# led.net
KiCad netlist of a schematic drawn in Altium Designer
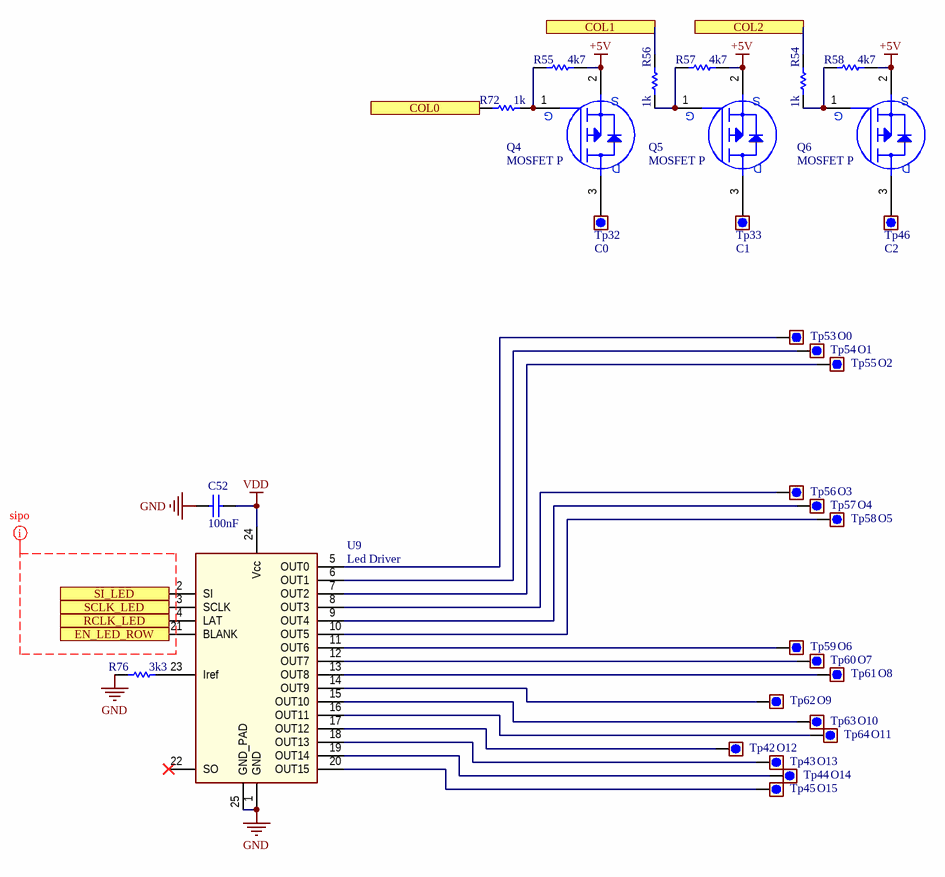
[diagram p0: led.SchDoc]

(export (version "E")
  (design (tool "Eeschema 10.0.6"))
  (components
    (comp (ref "C52")
      (value "100nF")
      (footprint "0603_[1608]")
      (description "Ceramic X7R 50V")
      (fields (field (name "PUBLISHER") "Altium Limited"))
      (libsource (lib "DEVELER_Library") (part "Cap"))
    )
    (comp (ref "Q4")
      (value "MOSFET P")
      (footprint "SOT-23")
      (description "IRLML5103TRPbF; DMG1013UW;")
      (libsource (lib "develer_library") (part "MOSFET-P 3pin"))
    )
    (comp (ref "Q5")
      (value "MOSFET P")
      (footprint "SOT-23")
      (description "IRLML5103TRPbF; DMG1013UW;")
      (libsource (lib "develer_library") (part "MOSFET-P 3pin"))
    )
    (comp (ref "Q6")
      (value "MOSFET P")
      (footprint "SOT-23")
      (description "IRLML5103TRPbF; DMG1013UW;")
      (libsource (lib "develer_library") (part "MOSFET-P 3pin"))
    )
    (comp (ref "R54")
      (value "1k")
      (footprint "0603_[1608]")
      (description "Resistor")
      (fields (field (name "PUBLISHER") "Altium Limited"))
      (libsource (lib "simboli") (part "Res1"))
    )
    (comp (ref "R55")
      (value "4k7")
      (footprint "0603_[1608]")
      (description "Resistor")
      (fields (field (name "PUBLISHER") "Altium Limited"))
      (libsource (lib "simboli") (part "Res1"))
    )
    (comp (ref "R56")
      (value "1k")
      (footprint "0603_[1608]")
      (description "Resistor")
      (fields (field (name "PUBLISHER") "Altium Limited"))
      (libsource (lib "simboli") (part "Res1"))
    )
    (comp (ref "R57")
      (value "4k7")
      (footprint "0603_[1608]")
      (description "Resistor")
      (fields (field (name "PUBLISHER") "Altium Limited"))
      (libsource (lib "simboli") (part "Res1"))
    )
    (comp (ref "R58")
      (value "4k7")
      (footprint "0603_[1608]")
      (description "Resistor")
      (fields (field (name "PUBLISHER") "Altium Limited"))
      (libsource (lib "simboli") (part "Res1"))
    )
    (comp (ref "R72")
      (value "1k")
      (footprint "0603_[1608]")
      (description "Resistor")
      (fields (field (name "PUBLISHER") "Altium Limited"))
      (libsource (lib "simboli") (part "Res1"))
    )
    (comp (ref "R76")
      (value "3k3")
      (footprint "0805_[2012]")
      (description "Resistor")
      (fields (field (name "PUBLISHER") "Altium Limited"))
      (libsource (lib "simboli") (part "Res1"))
    )
    (comp (ref "Tp32")
      (value "C0")
      (footprint "TEST_POINT_THD_D1.6mm_oval")
      (description "Test point")
      (libsource (lib "DEVELER_Library") (part "Test_point"))
    )
    (comp (ref "Tp33")
      (value "C1")
      (footprint "TEST_POINT_THD_D1.6mm_oval")
      (description "Test point")
      (libsource (lib "DEVELER_Library") (part "Test_point"))
    )
    (comp (ref "Tp42")
      (value "O12")
      (footprint "TEST_POINT_THD_D1.6mm_oval")
      (description "Test point")
      (libsource (lib "") (part "Test_point_1"))
    )
    (comp (ref "Tp43")
      (value "O13")
      (footprint "TEST_POINT_THD_D1.6mm_oval")
      (description "Test point")
      (libsource (lib "") (part "Test_point_1"))
    )
    (comp (ref "Tp44")
      (value "O14")
      (footprint "TEST_POINT_THD_D1.6mm_oval")
      (description "Test point")
      (libsource (lib "") (part "Test_point_1"))
    )
    (comp (ref "Tp45")
      (value "O15")
      (footprint "TEST_POINT_THD_D1.6mm_oval")
      (description "Test point")
      (libsource (lib "") (part "Test_point_1"))
    )
    (comp (ref "Tp46")
      (value "C2")
      (footprint "TEST_POINT_THD_D1.6mm_oval")
      (description "Test point")
      (libsource (lib "DEVELER_Library") (part "Test_point"))
    )
    (comp (ref "Tp53")
      (value "O0")
      (footprint "TEST_POINT_THD_D1.6mm_oval")
      (description "Test point")
      (libsource (lib "") (part "Test_point_1"))
    )
    (comp (ref "Tp54")
      (value "O1")
      (footprint "TEST_POINT_THD_D1.6mm_oval")
      (description "Test point")
      (libsource (lib "") (part "Test_point_1"))
    )
    (comp (ref "Tp55")
      (value "O2")
      (footprint "TEST_POINT_THD_D1.6mm_oval")
      (description "Test point")
      (libsource (lib "") (part "Test_point_1"))
    )
    (comp (ref "Tp56")
      (value "O3")
      (footprint "TEST_POINT_THD_D1.6mm_oval")
      (description "Test point")
      (libsource (lib "") (part "Test_point_1"))
    )
    (comp (ref "Tp57")
      (value "O4")
      (footprint "TEST_POINT_THD_D1.6mm_oval")
      (description "Test point")
      (libsource (lib "") (part "Test_point_1"))
    )
    (comp (ref "Tp58")
      (value "O5")
      (footprint "TEST_POINT_THD_D1.6mm_oval")
      (description "Test point")
      (libsource (lib "") (part "Test_point_1"))
    )
    (comp (ref "Tp59")
      (value "O6")
      (footprint "TEST_POINT_THD_D1.6mm_oval")
      (description "Test point")
      (libsource (lib "") (part "Test_point_1"))
    )
    (comp (ref "Tp60")
      (value "O7")
      (footprint "TEST_POINT_THD_D1.6mm_oval")
      (description "Test point")
      (libsource (lib "") (part "Test_point_1"))
    )
    (comp (ref "Tp61")
      (value "O8")
      (footprint "TEST_POINT_THD_D1.6mm_oval")
      (description "Test point")
      (libsource (lib "") (part "Test_point_1"))
    )
    (comp (ref "Tp62")
      (value "O9")
      (footprint "TEST_POINT_THD_D1.6mm_oval")
      (description "Test point")
      (libsource (lib "") (part "Test_point_1"))
    )
    (comp (ref "Tp63")
      (value "O10")
      (footprint "TEST_POINT_THD_D1.6mm_oval")
      (description "Test point")
      (libsource (lib "") (part "Test_point_1"))
    )
    (comp (ref "Tp64")
      (value "O11")
      (footprint "TEST_POINT_THD_D1.6mm_oval")
      (description "Test point")
      (libsource (lib "") (part "Test_point_1"))
    )
    (comp (ref "U9")
      (value "Led Driver")
      (footprint "TSOP65P640X120_HS-25N")
      (description "(Texas TLC5928; ST STP16CP05)")
      (libsource (lib "develer_library") (part "Led_driver"))
    )
  )
  (nets
    (net (code "1") (name "+5V") (class "Default")
      (node (ref "Q4") (pin "2") (pinfunction "S_2") (pintype "passive"))
      (node (ref "Q5") (pin "2") (pinfunction "S_2") (pintype "passive"))
      (node (ref "Q6") (pin "2") (pinfunction "S_2") (pintype "passive"))
      (node (ref "R55") (pin "1") (pinfunction "1_1") (pintype "passive"))
      (node (ref "R57") (pin "1") (pinfunction "1_1") (pintype "passive"))
      (node (ref "R58") (pin "1") (pinfunction "1_1") (pintype "passive"))
    )
    (net (code "2") (name "/COL0") (class "Default")
      (node (ref "R72") (pin "2") (pinfunction "2_2") (pintype "passive"))
    )
    (net (code "3") (name "/COL1") (class "Default")
      (node (ref "R56") (pin "1") (pinfunction "1_1") (pintype "passive"))
    )
    (net (code "4") (name "/COL2") (class "Default")
      (node (ref "R54") (pin "1") (pinfunction "1_1") (pintype "passive"))
    )
    (net (code "5") (name "/EN_LED_ROW") (class "Default")
      (node (ref "U9") (pin "21") (pinfunction "BLANK_21") (pintype "passive"))
    )
    (net (code "6") (name "/RCLK_LED") (class "Default")
      (node (ref "U9") (pin "4") (pinfunction "LAT_4") (pintype "passive"))
    )
    (net (code "7") (name "/SCLK_LED") (class "Default")
      (node (ref "U9") (pin "3") (pinfunction "SCLK_3") (pintype "passive"))
    )
    (net (code "8") (name "/SI_LED") (class "Default")
      (node (ref "U9") (pin "2") (pinfunction "SI_2") (pintype "passive"))
    )
    (net (code "9") (name "GND") (class "Default")
      (node (ref "C52") (pin "1") (pinfunction "1_1") (pintype "passive"))
      (node (ref "R76") (pin "1") (pinfunction "1_1") (pintype "passive"))
      (node (ref "U9") (pin "1") (pinfunction "GND_1") (pintype "passive"))
      (node (ref "U9") (pin "25") (pinfunction "GND_PAD_25") (pintype "passive"))
    )
    (net (code "10") (name "Net-(Q4-D)") (class "Default")
      (node (ref "Q4") (pin "3") (pinfunction "D_3") (pintype "passive"))
      (node (ref "Tp32") (pin "1") (pinfunction "1_1") (pintype "passive"))
    )
    (net (code "11") (name "Net-(Q4-G)") (class "Default")
      (node (ref "Q4") (pin "1") (pinfunction "G_1") (pintype "passive"))
      (node (ref "R55") (pin "2") (pinfunction "2_2") (pintype "passive"))
      (node (ref "R72") (pin "1") (pinfunction "1_1") (pintype "passive"))
    )
    (net (code "12") (name "Net-(Q5-D)") (class "Default")
      (node (ref "Q5") (pin "3") (pinfunction "D_3") (pintype "passive"))
      (node (ref "Tp33") (pin "1") (pinfunction "1_1") (pintype "passive"))
    )
    (net (code "13") (name "Net-(Q5-G)") (class "Default")
      (node (ref "Q5") (pin "1") (pinfunction "G_1") (pintype "passive"))
      (node (ref "R56") (pin "2") (pinfunction "2_2") (pintype "passive"))
      (node (ref "R57") (pin "2") (pinfunction "2_2") (pintype "passive"))
    )
    (net (code "14") (name "Net-(Q6-D)") (class "Default")
      (node (ref "Q6") (pin "3") (pinfunction "D_3") (pintype "passive"))
      (node (ref "Tp46") (pin "1") (pinfunction "1_1") (pintype "passive"))
    )
    (net (code "15") (name "Net-(Q6-G)") (class "Default")
      (node (ref "Q6") (pin "1") (pinfunction "G_1") (pintype "passive"))
      (node (ref "R54") (pin "2") (pinfunction "2_2") (pintype "passive"))
      (node (ref "R58") (pin "2") (pinfunction "2_2") (pintype "passive"))
    )
    (net (code "16") (name "Net-(U9-Iref)") (class "Default")
      (node (ref "R76") (pin "2") (pinfunction "2_2") (pintype "passive"))
      (node (ref "U9") (pin "23") (pinfunction "Iref_23") (pintype "passive"))
    )
    (net (code "17") (name "Net-(U9-OUT0)") (class "Default")
      (node (ref "Tp53") (pin "1") (pinfunction "1_1") (pintype "passive"))
      (node (ref "U9") (pin "5") (pinfunction "OUT0_5") (pintype "passive"))
    )
    (net (code "18") (name "Net-(U9-OUT1)") (class "Default")
      (node (ref "Tp54") (pin "1") (pinfunction "1_1") (pintype "passive"))
      (node (ref "U9") (pin "6") (pinfunction "OUT1_6") (pintype "passive"))
    )
    (net (code "19") (name "Net-(U9-OUT2)") (class "Default")
      (node (ref "Tp55") (pin "1") (pinfunction "1_1") (pintype "passive"))
      (node (ref "U9") (pin "7") (pinfunction "OUT2_7") (pintype "passive"))
    )
    (net (code "20") (name "Net-(U9-OUT3)") (class "Default")
      (node (ref "Tp56") (pin "1") (pinfunction "1_1") (pintype "passive"))
      (node (ref "U9") (pin "8") (pinfunction "OUT3_8") (pintype "passive"))
    )
    (net (code "21") (name "Net-(U9-OUT4)") (class "Default")
      (node (ref "Tp57") (pin "1") (pinfunction "1_1") (pintype "passive"))
      (node (ref "U9") (pin "9") (pinfunction "OUT4_9") (pintype "passive"))
    )
    (net (code "22") (name "Net-(U9-OUT5)") (class "Default")
      (node (ref "Tp58") (pin "1") (pinfunction "1_1") (pintype "passive"))
      (node (ref "U9") (pin "10") (pinfunction "OUT5_10") (pintype "passive"))
    )
    (net (code "23") (name "Net-(U9-OUT6)") (class "Default")
      (node (ref "Tp59") (pin "1") (pinfunction "1_1") (pintype "passive"))
      (node (ref "U9") (pin "11") (pinfunction "OUT6_11") (pintype "passive"))
    )
    (net (code "24") (name "Net-(U9-OUT7)") (class "Default")
      (node (ref "Tp60") (pin "1") (pinfunction "1_1") (pintype "passive"))
      (node (ref "U9") (pin "12") (pinfunction "OUT7_12") (pintype "passive"))
    )
    (net (code "25") (name "Net-(U9-OUT8)") (class "Default")
      (node (ref "Tp61") (pin "1") (pinfunction "1_1") (pintype "passive"))
      (node (ref "U9") (pin "13") (pinfunction "OUT8_13") (pintype "passive"))
    )
    (net (code "26") (name "Net-(U9-OUT9)") (class "Default")
      (node (ref "Tp62") (pin "1") (pinfunction "1_1") (pintype "passive"))
      (node (ref "U9") (pin "14") (pinfunction "OUT9_14") (pintype "passive"))
    )
    (net (code "27") (name "Net-(U9-OUT10)") (class "Default")
      (node (ref "Tp63") (pin "1") (pinfunction "1_1") (pintype "passive"))
      (node (ref "U9") (pin "15") (pinfunction "OUT10_15") (pintype "passive"))
    )
    (net (code "28") (name "Net-(U9-OUT11)") (class "Default")
      (node (ref "Tp64") (pin "1") (pinfunction "1_1") (pintype "passive"))
      (node (ref "U9") (pin "16") (pinfunction "OUT11_16") (pintype "passive"))
    )
    (net (code "29") (name "Net-(U9-OUT12)") (class "Default")
      (node (ref "Tp42") (pin "1") (pinfunction "1_1") (pintype "passive"))
      (node (ref "U9") (pin "17") (pinfunction "OUT12_17") (pintype "passive"))
    )
    (net (code "30") (name "Net-(U9-OUT13)") (class "Default")
      (node (ref "Tp43") (pin "1") (pinfunction "1_1") (pintype "passive"))
      (node (ref "U9") (pin "18") (pinfunction "OUT13_18") (pintype "passive"))
    )
    (net (code "31") (name "Net-(U9-OUT14)") (class "Default")
      (node (ref "Tp44") (pin "1") (pinfunction "1_1") (pintype "passive"))
      (node (ref "U9") (pin "19") (pinfunction "OUT14_19") (pintype "passive"))
    )
    (net (code "32") (name "Net-(U9-OUT15)") (class "Default")
      (node (ref "Tp45") (pin "1") (pinfunction "1_1") (pintype "passive"))
      (node (ref "U9") (pin "20") (pinfunction "OUT15_20") (pintype "passive"))
    )
    (net (code "33") (name "VDD") (class "Default")
      (node (ref "C52") (pin "2") (pinfunction "2_2") (pintype "passive"))
      (node (ref "U9") (pin "24") (pinfunction "Vcc_24") (pintype "passive"))
    )
    (net (code "34") (name "unconnected-(U9-SO-Pad22)") (class "Default")
      (node (ref "U9") (pin "22") (pinfunction "SO_22") (pintype "passive+no_connect"))
    )
  )
)
